# G882X.net
KiCad netlist of a schematic drawn in EAGLE
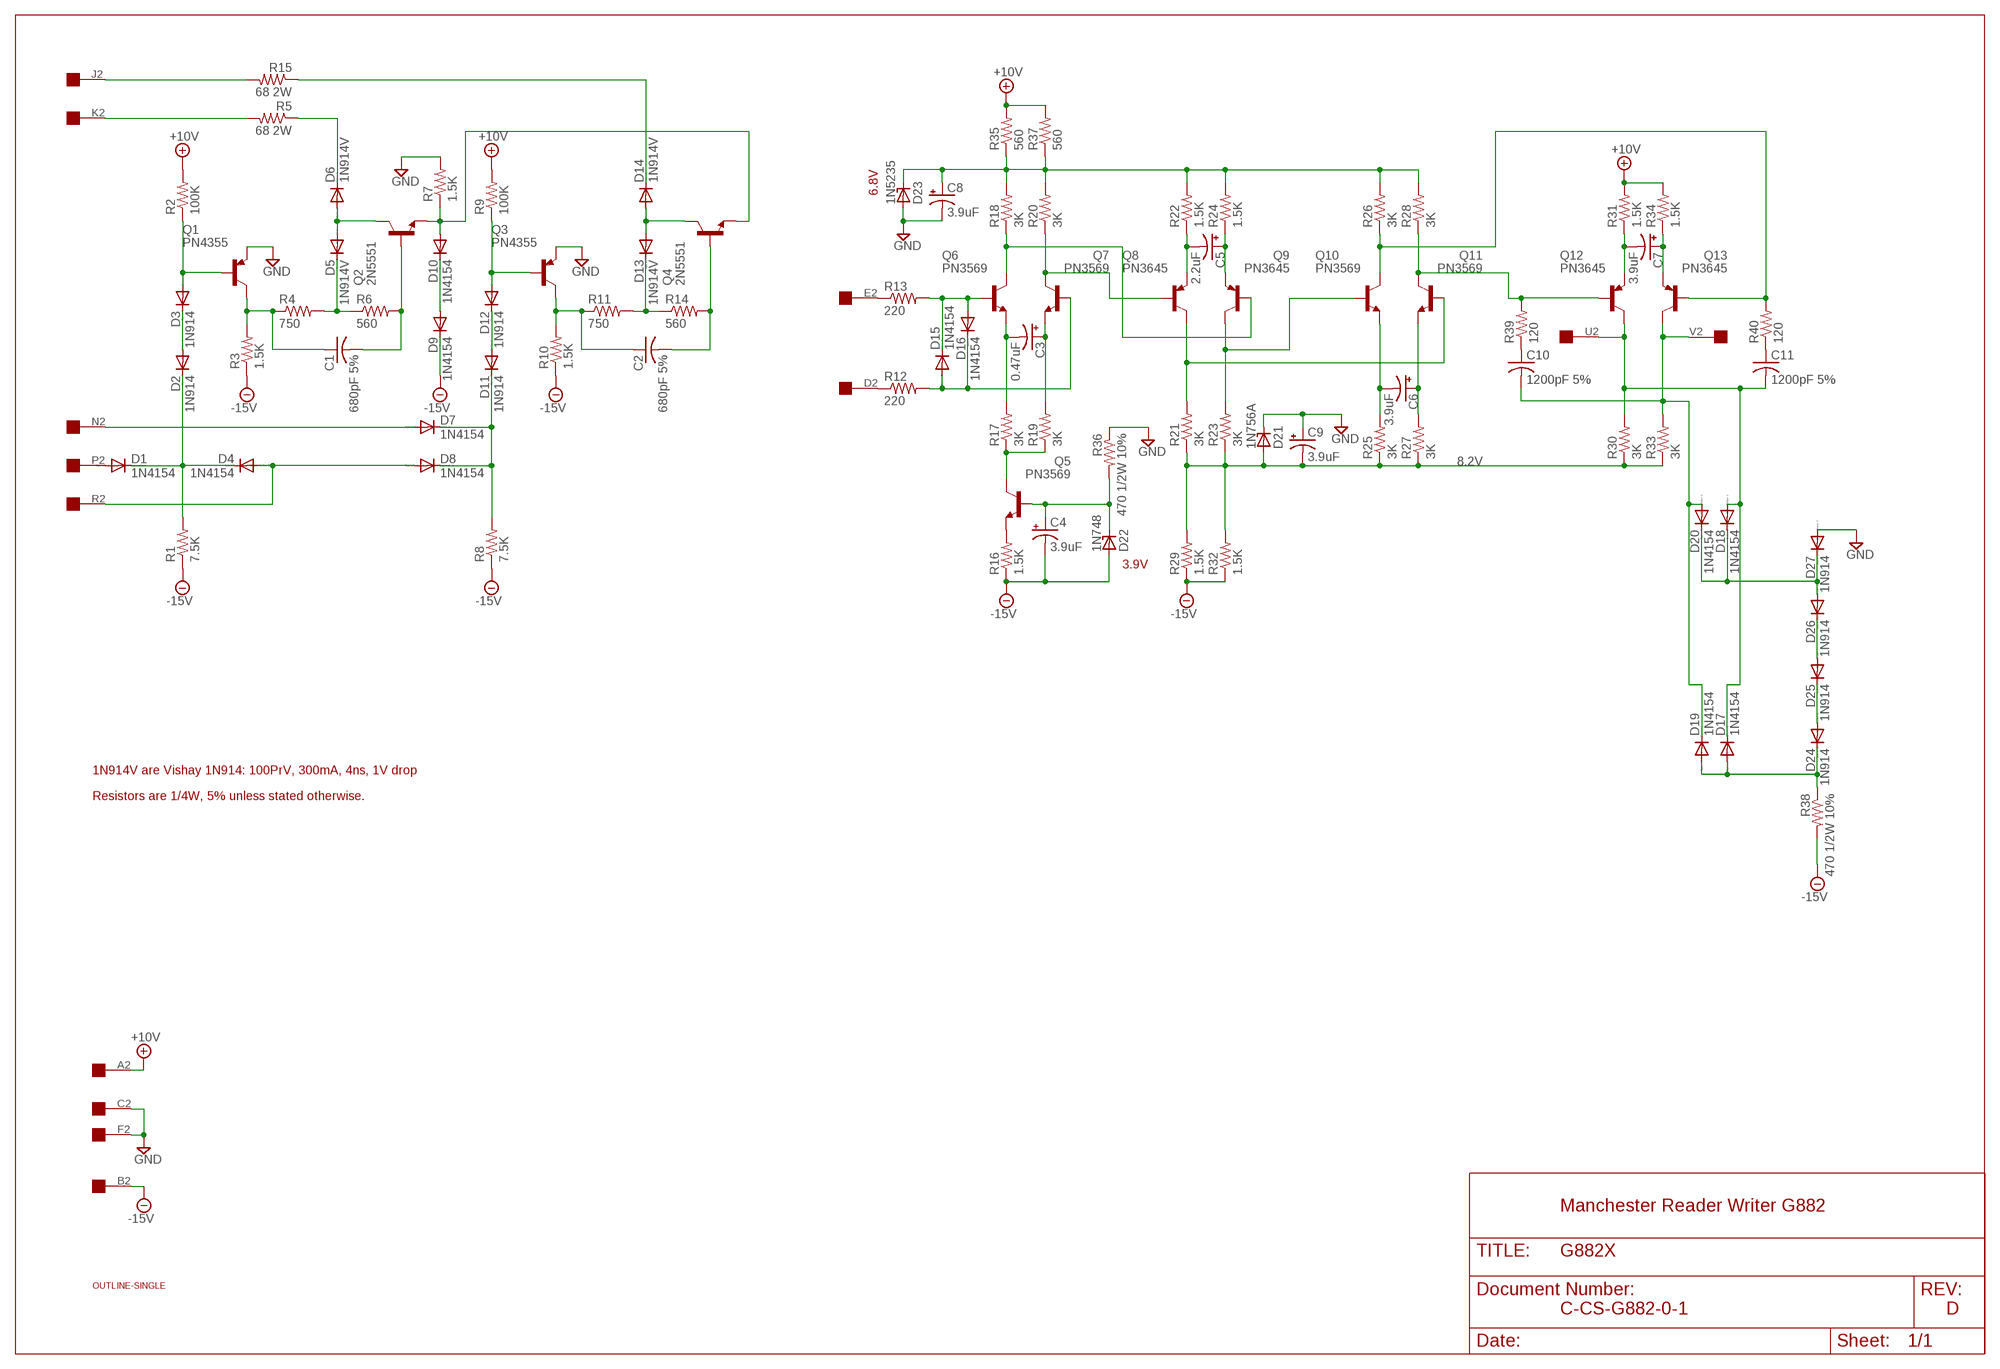
[diagram p0: schematic, sheet 1]

(export (version "E")
  (design (tool "Eeschema 10.0.6"))
  (components
    (comp (ref "C1")
      (value "680pF 5%")
      (footprint "eagle-import:C050-025X075")
      (libsource (lib "eagle-import") (part "C-US050-025X075"))
    )
    (comp (ref "C2")
      (value "680pF 5%")
      (footprint "eagle-import:C050-025X075")
      (libsource (lib "eagle-import") (part "C-US050-025X075"))
    )
    (comp (ref "C3")
      (value "0.47uF")
      (footprint "eagle-import:E12-4")
      (libsource (lib "eagle-import") (part "CPOL-USE12-4AXIAL"))
    )
    (comp (ref "C4")
      (value "3.9uF")
      (footprint "eagle-import:E12-4")
      (libsource (lib "eagle-import") (part "CPOL-USE12-4AXIAL"))
    )
    (comp (ref "C5")
      (value "2.2uF")
      (footprint "eagle-import:E12-4")
      (libsource (lib "eagle-import") (part "CPOL-USE12-4AXIAL"))
    )
    (comp (ref "C6")
      (value "3.9uF")
      (footprint "eagle-import:E12-4")
      (libsource (lib "eagle-import") (part "CPOL-USE12-4AXIAL"))
    )
    (comp (ref "C7")
      (value "3.9uF")
      (footprint "eagle-import:E12-4")
      (libsource (lib "eagle-import") (part "CPOL-USE12-4AXIAL"))
    )
    (comp (ref "C8")
      (value "3.9uF")
      (footprint "eagle-import:E12-4")
      (libsource (lib "eagle-import") (part "CPOL-USE12-4AXIAL"))
    )
    (comp (ref "C9")
      (value "3.9uF")
      (footprint "eagle-import:E12-4")
      (libsource (lib "eagle-import") (part "CPOL-USE12-4AXIAL"))
    )
    (comp (ref "C10")
      (value "1200pF 5%")
      (footprint "eagle-import:C050-025X075")
      (libsource (lib "eagle-import") (part "C-US050-025X075"))
    )
    (comp (ref "C11")
      (value "1200pF 5%")
      (footprint "eagle-import:C050-025X075")
      (libsource (lib "eagle-import") (part "C-US050-025X075"))
    )
    (comp (ref "D1")
      (value "1N4154")
      (footprint "eagle-import:DO35-10")
      (libsource (lib "eagle-import") (part "1N4148DO35-10"))
    )
    (comp (ref "D2")
      (value "1N914")
      (footprint "eagle-import:DO35-10")
      (libsource (lib "eagle-import") (part "1N4148DO35-10"))
    )
    (comp (ref "D3")
      (value "1N914")
      (footprint "eagle-import:DO35-10")
      (libsource (lib "eagle-import") (part "1N4148DO35-10"))
    )
    (comp (ref "D4")
      (value "1N4154")
      (footprint "eagle-import:DO35-10")
      (libsource (lib "eagle-import") (part "1N4148DO35-10"))
    )
    (comp (ref "D5")
      (value "1N914V")
      (footprint "eagle-import:DO35-10")
      (libsource (lib "eagle-import") (part "1N4148DO35-10"))
    )
    (comp (ref "D6")
      (value "1N914V")
      (footprint "eagle-import:DO35-10")
      (libsource (lib "eagle-import") (part "1N4148DO35-10"))
    )
    (comp (ref "D7")
      (value "1N4154")
      (footprint "eagle-import:DO35-10")
      (libsource (lib "eagle-import") (part "1N4148DO35-10"))
    )
    (comp (ref "D8")
      (value "1N4154")
      (footprint "eagle-import:DO35-10")
      (libsource (lib "eagle-import") (part "1N4148DO35-10"))
    )
    (comp (ref "D9")
      (value "1N4154")
      (footprint "eagle-import:DO35-10")
      (libsource (lib "eagle-import") (part "1N4148DO35-10"))
    )
    (comp (ref "D10")
      (value "1N4154")
      (footprint "eagle-import:DO35-10")
      (libsource (lib "eagle-import") (part "1N4148DO35-10"))
    )
    (comp (ref "D11")
      (value "1N914")
      (footprint "eagle-import:DO35-10")
      (libsource (lib "eagle-import") (part "1N4148DO35-10"))
    )
    (comp (ref "D12")
      (value "1N914")
      (footprint "eagle-import:DO35-10")
      (libsource (lib "eagle-import") (part "1N4148DO35-10"))
    )
    (comp (ref "D13")
      (value "1N914V")
      (footprint "eagle-import:DO35-10")
      (libsource (lib "eagle-import") (part "1N4148DO35-10"))
    )
    (comp (ref "D14")
      (value "1N914V")
      (footprint "eagle-import:DO35-10")
      (libsource (lib "eagle-import") (part "1N4148DO35-10"))
    )
    (comp (ref "D15")
      (value "1N4154")
      (footprint "eagle-import:DO35-10")
      (libsource (lib "eagle-import") (part "1N4148DO35-10"))
    )
    (comp (ref "D16")
      (value "1N4154")
      (footprint "eagle-import:DO35-10")
      (libsource (lib "eagle-import") (part "1N4148DO35-10"))
    )
    (comp (ref "D17")
      (value "1N4154")
      (footprint "eagle-import:DO35-10")
      (libsource (lib "eagle-import") (part "1N4148DO35-10"))
    )
    (comp (ref "D18")
      (value "1N4154")
      (footprint "eagle-import:DO35-10")
      (libsource (lib "eagle-import") (part "1N4148DO35-10"))
    )
    (comp (ref "D19")
      (value "1N4154")
      (footprint "eagle-import:DO35-10")
      (libsource (lib "eagle-import") (part "1N4148DO35-10"))
    )
    (comp (ref "D20")
      (value "1N4154")
      (footprint "eagle-import:DO35-10")
      (libsource (lib "eagle-import") (part "1N4148DO35-10"))
    )
    (comp (ref "D21")
      (value "1N756A")
      (footprint "eagle-import:DO35Z10")
      (libsource (lib "eagle-import") (part "ZENER-DIODEDO35Z10"))
    )
    (comp (ref "D22")
      (value "1N748")
      (footprint "eagle-import:DO35Z10")
      (libsource (lib "eagle-import") (part "ZENER-DIODEDO35Z10"))
    )
    (comp (ref "D23")
      (value "1N5235")
      (footprint "eagle-import:DO35Z10")
      (libsource (lib "eagle-import") (part "ZENER-DIODEDO35Z10"))
    )
    (comp (ref "D24")
      (value "1N914")
      (footprint "eagle-import:DO35-10")
      (libsource (lib "eagle-import") (part "1N4148DO35-10"))
    )
    (comp (ref "D25")
      (value "1N914")
      (footprint "eagle-import:DO35-10")
      (libsource (lib "eagle-import") (part "1N4148DO35-10"))
    )
    (comp (ref "D26")
      (value "1N914")
      (footprint "eagle-import:DO35-10")
      (libsource (lib "eagle-import") (part "1N4148DO35-10"))
    )
    (comp (ref "D27")
      (value "1N914")
      (footprint "eagle-import:DO35-10")
      (libsource (lib "eagle-import") (part "1N4148DO35-10"))
    )
    (comp (ref "Q1")
      (value "PN4355")
      (footprint "eagle-import:TO39")
      (libsource (lib "eagle-import") (part "2N3635"))
    )
    (comp (ref "Q2")
      (value "2N5551")
      (footprint "eagle-import:TO5")
      (libsource (lib "eagle-import") (part "2N2102"))
    )
    (comp (ref "Q3")
      (value "PN4355")
      (footprint "eagle-import:TO39")
      (libsource (lib "eagle-import") (part "2N3635"))
    )
    (comp (ref "Q4")
      (value "2N5551")
      (footprint "eagle-import:TO5")
      (libsource (lib "eagle-import") (part "2N2102"))
    )
    (comp (ref "Q5")
      (value "PN3569")
      (footprint "eagle-import:TO5")
      (libsource (lib "eagle-import") (part "2N2102"))
    )
    (comp (ref "Q6")
      (value "PN3569")
      (footprint "eagle-import:TO5")
      (libsource (lib "eagle-import") (part "2N2102"))
    )
    (comp (ref "Q7")
      (value "PN3569")
      (footprint "eagle-import:TO5")
      (libsource (lib "eagle-import") (part "2N2102"))
    )
    (comp (ref "Q8")
      (value "PN3645")
      (footprint "eagle-import:TO39")
      (libsource (lib "eagle-import") (part "2N3635"))
    )
    (comp (ref "Q9")
      (value "PN3645")
      (footprint "eagle-import:TO39")
      (libsource (lib "eagle-import") (part "2N3635"))
    )
    (comp (ref "Q10")
      (value "PN3569")
      (footprint "eagle-import:TO5")
      (libsource (lib "eagle-import") (part "2N2102"))
    )
    (comp (ref "Q11")
      (value "PN3569")
      (footprint "eagle-import:TO5")
      (libsource (lib "eagle-import") (part "2N2102"))
    )
    (comp (ref "Q12")
      (value "PN3645")
      (footprint "eagle-import:TO39")
      (libsource (lib "eagle-import") (part "2N3635"))
    )
    (comp (ref "Q13")
      (value "PN3645")
      (footprint "eagle-import:TO39")
      (libsource (lib "eagle-import") (part "2N3635"))
    )
    (comp (ref "R1")
      (value "7.5K")
      (footprint "eagle-import:0207_10")
      (libsource (lib "eagle-import") (part "R-US_0207/10"))
    )
    (comp (ref "R2")
      (value "100K")
      (footprint "eagle-import:0207_10")
      (libsource (lib "eagle-import") (part "R-US_0207/10"))
    )
    (comp (ref "R3")
      (value "1.5K")
      (footprint "eagle-import:0207_10")
      (libsource (lib "eagle-import") (part "R-US_0207/10"))
    )
    (comp (ref "R4")
      (value "750")
      (footprint "eagle-import:0207_10")
      (libsource (lib "eagle-import") (part "R-US_0207/10"))
    )
    (comp (ref "R5")
      (value "68 2W")
      (footprint "eagle-import:P0817_22")
      (libsource (lib "eagle-import") (part "R-US_0817/22"))
    )
    (comp (ref "R6")
      (value "560")
      (footprint "eagle-import:0207_10")
      (libsource (lib "eagle-import") (part "R-US_0207/10"))
    )
    (comp (ref "R7")
      (value "1.5K")
      (footprint "eagle-import:0207_10")
      (libsource (lib "eagle-import") (part "R-US_0207/10"))
    )
    (comp (ref "R8")
      (value "7.5K")
      (footprint "eagle-import:0207_10")
      (libsource (lib "eagle-import") (part "R-US_0207/10"))
    )
    (comp (ref "R9")
      (value "100K")
      (footprint "eagle-import:0207_10")
      (libsource (lib "eagle-import") (part "R-US_0207/10"))
    )
    (comp (ref "R10")
      (value "1.5K")
      (footprint "eagle-import:0207_10")
      (libsource (lib "eagle-import") (part "R-US_0207/10"))
    )
    (comp (ref "R11")
      (value "750")
      (footprint "eagle-import:0207_10")
      (libsource (lib "eagle-import") (part "R-US_0207/10"))
    )
    (comp (ref "R12")
      (value "220")
      (footprint "eagle-import:0207_10")
      (libsource (lib "eagle-import") (part "R-US_0207/10"))
    )
    (comp (ref "R13")
      (value "220")
      (footprint "eagle-import:0207_10")
      (libsource (lib "eagle-import") (part "R-US_0207/10"))
    )
    (comp (ref "R14")
      (value "560")
      (footprint "eagle-import:0207_10")
      (libsource (lib "eagle-import") (part "R-US_0207/10"))
    )
    (comp (ref "R15")
      (value "68 2W")
      (footprint "eagle-import:P0817_22")
      (libsource (lib "eagle-import") (part "R-US_0817/22"))
    )
    (comp (ref "R16")
      (value "1.5K")
      (footprint "eagle-import:0207_10")
      (libsource (lib "eagle-import") (part "R-US_0207/10"))
    )
    (comp (ref "R17")
      (value "3K")
      (footprint "eagle-import:0207_10")
      (libsource (lib "eagle-import") (part "R-US_0207/10"))
    )
    (comp (ref "R18")
      (value "3K")
      (footprint "eagle-import:0207_10")
      (libsource (lib "eagle-import") (part "R-US_0207/10"))
    )
    (comp (ref "R19")
      (value "3K")
      (footprint "eagle-import:0207_10")
      (libsource (lib "eagle-import") (part "R-US_0207/10"))
    )
    (comp (ref "R20")
      (value "3K")
      (footprint "eagle-import:0207_10")
      (libsource (lib "eagle-import") (part "R-US_0207/10"))
    )
    (comp (ref "R21")
      (value "3K")
      (footprint "eagle-import:0207_10")
      (libsource (lib "eagle-import") (part "R-US_0207/10"))
    )
    (comp (ref "R22")
      (value "1.5K")
      (footprint "eagle-import:0207_10")
      (libsource (lib "eagle-import") (part "R-US_0207/10"))
    )
    (comp (ref "R23")
      (value "3K")
      (footprint "eagle-import:0207_10")
      (libsource (lib "eagle-import") (part "R-US_0207/10"))
    )
    (comp (ref "R24")
      (value "1.5K")
      (footprint "eagle-import:0207_10")
      (libsource (lib "eagle-import") (part "R-US_0207/10"))
    )
    (comp (ref "R25")
      (value "3K")
      (footprint "eagle-import:0207_10")
      (libsource (lib "eagle-import") (part "R-US_0207/10"))
    )
    (comp (ref "R26")
      (value "3K")
      (footprint "eagle-import:0207_10")
      (libsource (lib "eagle-import") (part "R-US_0207/10"))
    )
    (comp (ref "R27")
      (value "3K")
      (footprint "eagle-import:0207_10")
      (libsource (lib "eagle-import") (part "R-US_0207/10"))
    )
    (comp (ref "R28")
      (value "3K")
      (footprint "eagle-import:0207_10")
      (libsource (lib "eagle-import") (part "R-US_0207/10"))
    )
    (comp (ref "R29")
      (value "1.5K")
      (footprint "eagle-import:0207_10")
      (libsource (lib "eagle-import") (part "R-US_0207/10"))
    )
    (comp (ref "R30")
      (value "3K")
      (footprint "eagle-import:0207_10")
      (libsource (lib "eagle-import") (part "R-US_0207/10"))
    )
    (comp (ref "R31")
      (value "1.5K")
      (footprint "eagle-import:0207_10")
      (libsource (lib "eagle-import") (part "R-US_0207/10"))
    )
    (comp (ref "R32")
      (value "1.5K")
      (footprint "eagle-import:0207_10")
      (libsource (lib "eagle-import") (part "R-US_0207/10"))
    )
    (comp (ref "R33")
      (value "3K")
      (footprint "eagle-import:0207_10")
      (libsource (lib "eagle-import") (part "R-US_0207/10"))
    )
    (comp (ref "R34")
      (value "1.5K")
      (footprint "eagle-import:0207_10")
      (libsource (lib "eagle-import") (part "R-US_0207/10"))
    )
    (comp (ref "R35")
      (value "560")
      (footprint "eagle-import:0207_10")
      (libsource (lib "eagle-import") (part "R-US_0207/10"))
    )
    (comp (ref "R36")
      (value "470 1/2W 10%")
      (footprint "eagle-import:0309_12")
      (libsource (lib "eagle-import") (part "R-US_0309/12"))
    )
    (comp (ref "R37")
      (value "560")
      (footprint "eagle-import:0207_10")
      (libsource (lib "eagle-import") (part "R-US_0207/10"))
    )
    (comp (ref "R38")
      (value "470 1/2W 10%")
      (footprint "eagle-import:0309_12")
      (libsource (lib "eagle-import") (part "R-US_0309/12"))
    )
    (comp (ref "R39")
      (value "120")
      (footprint "eagle-import:0207_10")
      (libsource (lib "eagle-import") (part "R-US_0207/10"))
    )
    (comp (ref "R40")
      (value "120")
      (footprint "eagle-import:0207_10")
      (libsource (lib "eagle-import") (part "R-US_0207/10"))
    )
    (comp (ref "U$1")
      (value "OUTLINE-SINGLE")
      (footprint "eagle-import:SINGLE")
      (libsource (lib "eagle-import") (part "OUTLINE-SINGLE"))
    )
    (comp (ref "U$2")
      (value "EDGE-1")
      (footprint "eagle-import:EDGE-CON1")
      (libsource (lib "eagle-import") (part "EDGE-1"))
    )
  )
  (nets
    (net (code "1") (name "+10V") (class "Default")
      (node (ref "R2") (pin "2") (pinfunction "2_2") (pintype "passive"))
      (node (ref "R31") (pin "2") (pinfunction "2_2") (pintype "passive"))
      (node (ref "R34") (pin "2") (pinfunction "2_2") (pintype "passive"))
      (node (ref "R35") (pin "2") (pinfunction "2_2") (pintype "passive"))
      (node (ref "R37") (pin "2") (pinfunction "2_2") (pintype "passive"))
      (node (ref "R9") (pin "2") (pinfunction "2_2") (pintype "passive"))
      (node (ref "U$2") (pin "A2") (pinfunction "1_A2") (pintype "bidirectional"))
    )
    (net (code "2") (name "-15V") (class "Default")
      (node (ref "C4") (pin "-") (pinfunction "-_-") (pintype "passive"))
      (node (ref "D22") (pin "A") (pinfunction "A_A") (pintype "passive"))
      (node (ref "D9") (pin "C") (pinfunction "C_C") (pintype "passive"))
      (node (ref "R1") (pin "1") (pinfunction "1_1") (pintype "passive"))
      (node (ref "R10") (pin "1") (pinfunction "1_1") (pintype "passive"))
      (node (ref "R16") (pin "1") (pinfunction "1_1") (pintype "passive"))
      (node (ref "R29") (pin "1") (pinfunction "1_1") (pintype "passive"))
      (node (ref "R3") (pin "1") (pinfunction "1_1") (pintype "passive"))
      (node (ref "R32") (pin "1") (pinfunction "1_1") (pintype "passive"))
      (node (ref "R38") (pin "2") (pinfunction "2_2") (pintype "passive"))
      (node (ref "R8") (pin "1") (pinfunction "1_1") (pintype "passive"))
      (node (ref "U$2") (pin "B2") (pinfunction "1_B2") (pintype "bidirectional"))
    )
    (net (code "3") (name "/8.2V") (class "Default")
      (node (ref "C9") (pin "-") (pinfunction "-_-") (pintype "passive"))
      (node (ref "D21") (pin "A") (pinfunction "A_A") (pintype "passive"))
      (node (ref "R21") (pin "1") (pinfunction "1_1") (pintype "passive"))
      (node (ref "R23") (pin "1") (pinfunction "1_1") (pintype "passive"))
      (node (ref "R25") (pin "1") (pinfunction "1_1") (pintype "passive"))
      (node (ref "R27") (pin "1") (pinfunction "1_1") (pintype "passive"))
      (node (ref "R29") (pin "2") (pinfunction "2_2") (pintype "passive"))
      (node (ref "R30") (pin "1") (pinfunction "1_1") (pintype "passive"))
      (node (ref "R32") (pin "2") (pinfunction "2_2") (pintype "passive"))
      (node (ref "R33") (pin "1") (pinfunction "1_1") (pintype "passive"))
    )
    (net (code "4") (name "GND") (class "Default")
      (node (ref "C8") (pin "-") (pinfunction "-_-") (pintype "passive"))
      (node (ref "C9") (pin "+") (pinfunction "+_+") (pintype "passive"))
      (node (ref "D21") (pin "C") (pinfunction "C_C") (pintype "passive"))
      (node (ref "D23") (pin "A") (pinfunction "A_A") (pintype "passive"))
      (node (ref "D27") (pin "A") (pinfunction "A_A") (pintype "passive"))
      (node (ref "Q1") (pin "1") (pinfunction "E_1") (pintype "passive"))
      (node (ref "Q3") (pin "1") (pinfunction "E_1") (pintype "passive"))
      (node (ref "R36") (pin "1") (pinfunction "1_1") (pintype "passive"))
      (node (ref "R7") (pin "2") (pinfunction "2_2") (pintype "passive"))
      (node (ref "U$2") (pin "C2") (pinfunction "1_C2") (pintype "bidirectional"))
      (node (ref "U$2") (pin "F2") (pinfunction "1_F2") (pintype "bidirectional"))
    )
    (net (code "5") (name "Net-(C8-Pad+)") (class "Default")
      (node (ref "C8") (pin "+") (pinfunction "+_+") (pintype "passive"))
      (node (ref "D23") (pin "C") (pinfunction "C_C") (pintype "passive"))
      (node (ref "R18") (pin "2") (pinfunction "2_2") (pintype "passive"))
      (node (ref "R20") (pin "2") (pinfunction "2_2") (pintype "passive"))
      (node (ref "R22") (pin "2") (pinfunction "2_2") (pintype "passive"))
      (node (ref "R24") (pin "2") (pinfunction "2_2") (pintype "passive"))
      (node (ref "R26") (pin "2") (pinfunction "2_2") (pintype "passive"))
      (node (ref "R28") (pin "2") (pinfunction "2_2") (pintype "passive"))
      (node (ref "R35") (pin "1") (pinfunction "1_1") (pintype "passive"))
      (node (ref "R37") (pin "1") (pinfunction "1_1") (pintype "passive"))
    )
    (net (code "6") (name "Net-(C10-Pad1)") (class "Default")
      (node (ref "C10") (pin "1") (pinfunction "1_1") (pintype "passive"))
      (node (ref "R39") (pin "1") (pinfunction "1_1") (pintype "passive"))
    )
    (net (code "7") (name "Net-(C11-Pad1)") (class "Default")
      (node (ref "C11") (pin "1") (pinfunction "1_1") (pintype "passive"))
      (node (ref "R40") (pin "1") (pinfunction "1_1") (pintype "passive"))
    )
    (net (code "8") (name "Net-(D1-PadC)") (class "Default")
      (node (ref "D1") (pin "C") (pinfunction "C_C") (pintype "passive"))
      (node (ref "D2") (pin "C") (pinfunction "C_C") (pintype "passive"))
      (node (ref "D4") (pin "C") (pinfunction "C_C") (pintype "passive"))
      (node (ref "R1") (pin "2") (pinfunction "2_2") (pintype "passive"))
    )
    (net (code "9") (name "Net-(D2-PadA)") (class "Default")
      (node (ref "D2") (pin "A") (pinfunction "A_A") (pintype "passive"))
      (node (ref "D3") (pin "C") (pinfunction "C_C") (pintype "passive"))
    )
    (net (code "10") (name "Net-(D5-PadC)") (class "Default")
      (node (ref "D5") (pin "C") (pinfunction "C_C") (pintype "passive"))
      (node (ref "R4") (pin "2") (pinfunction "2_2") (pintype "passive"))
      (node (ref "R6") (pin "1") (pinfunction "1_1") (pintype "passive"))
    )
    (net (code "11") (name "Net-(D6-PadC)") (class "Default")
      (node (ref "D6") (pin "C") (pinfunction "C_C") (pintype "passive"))
      (node (ref "R5") (pin "1") (pinfunction "1_1") (pintype "passive"))
    )
    (net (code "12") (name "Net-(D10-PadC)") (class "Default")
      (node (ref "D10") (pin "C") (pinfunction "C_C") (pintype "passive"))
      (node (ref "D9") (pin "A") (pinfunction "A_A") (pintype "passive"))
    )
    (net (code "13") (name "Net-(D11-PadA)") (class "Default")
      (node (ref "D11") (pin "A") (pinfunction "A_A") (pintype "passive"))
      (node (ref "D12") (pin "C") (pinfunction "C_C") (pintype "passive"))
    )
    (net (code "14") (name "Net-(D11-PadC)") (class "Default")
      (node (ref "D11") (pin "C") (pinfunction "C_C") (pintype "passive"))
      (node (ref "D7") (pin "C") (pinfunction "C_C") (pintype "passive"))
      (node (ref "D8") (pin "C") (pinfunction "C_C") (pintype "passive"))
      (node (ref "R8") (pin "2") (pinfunction "2_2") (pintype "passive"))
    )
    (net (code "15") (name "Net-(D13-PadC)") (class "Default")
      (node (ref "D13") (pin "C") (pinfunction "C_C") (pintype "passive"))
      (node (ref "R11") (pin "2") (pinfunction "2_2") (pintype "passive"))
      (node (ref "R14") (pin "1") (pinfunction "1_1") (pintype "passive"))
    )
    (net (code "16") (name "Net-(D14-PadC)") (class "Default")
      (node (ref "D14") (pin "C") (pinfunction "C_C") (pintype "passive"))
      (node (ref "R15") (pin "1") (pinfunction "1_1") (pintype "passive"))
    )
    (net (code "17") (name "Net-(D17-PadA)") (class "Default")
      (node (ref "D17") (pin "A") (pinfunction "A_A") (pintype "passive"))
      (node (ref "D19") (pin "A") (pinfunction "A_A") (pintype "passive"))
      (node (ref "D24") (pin "C") (pinfunction "C_C") (pintype "passive"))
      (node (ref "R38") (pin "1") (pinfunction "1_1") (pintype "passive"))
    )
    (net (code "18") (name "Net-(D18-PadC)") (class "Default")
      (node (ref "D18") (pin "C") (pinfunction "C_C") (pintype "passive"))
      (node (ref "D20") (pin "C") (pinfunction "C_C") (pintype "passive"))
      (node (ref "D26") (pin "A") (pinfunction "A_A") (pintype "passive"))
      (node (ref "D27") (pin "C") (pinfunction "C_C") (pintype "passive"))
    )
    (net (code "19") (name "Net-(D24-PadA)") (class "Default")
      (node (ref "D24") (pin "A") (pinfunction "A_A") (pintype "passive"))
      (node (ref "D25") (pin "C") (pinfunction "C_C") (pintype "passive"))
    )
    (net (code "20") (name "Net-(D25-PadA)") (class "Default")
      (node (ref "D25") (pin "A") (pinfunction "A_A") (pintype "passive"))
      (node (ref "D26") (pin "C") (pinfunction "C_C") (pintype "passive"))
    )
    (net (code "21") (name "Net-(Q1-B)") (class "Default")
      (node (ref "D3") (pin "A") (pinfunction "A_A") (pintype "passive"))
      (node (ref "Q1") (pin "2") (pinfunction "B_2") (pintype "passive"))
      (node (ref "R2") (pin "1") (pinfunction "1_1") (pintype "passive"))
    )
    (net (code "22") (name "Net-(Q1-C)") (class "Default")
      (node (ref "C1") (pin "1") (pinfunction "1_1") (pintype "passive"))
      (node (ref "Q1") (pin "3") (pinfunction "C_3") (pintype "passive"))
      (node (ref "R3") (pin "2") (pinfunction "2_2") (pintype "passive"))
      (node (ref "R4") (pin "1") (pinfunction "1_1") (pintype "passive"))
    )
    (net (code "23") (name "Net-(Q2-B)") (class "Default")
      (node (ref "C1") (pin "2") (pinfunction "2_2") (pintype "passive"))
      (node (ref "Q2") (pin "2") (pinfunction "B_2") (pintype "passive"))
      (node (ref "R6") (pin "2") (pinfunction "2_2") (pintype "passive"))
    )
    (net (code "24") (name "Net-(Q2-C)") (class "Default")
      (node (ref "D5") (pin "A") (pinfunction "A_A") (pintype "passive"))
      (node (ref "D6") (pin "A") (pinfunction "A_A") (pintype "passive"))
      (node (ref "Q2") (pin "3") (pinfunction "C_3") (pintype "passive"))
    )
    (net (code "25") (name "Net-(Q2-E)") (class "Default")
      (node (ref "D10") (pin "A") (pinfunction "A_A") (pintype "passive"))
      (node (ref "Q2") (pin "1") (pinfunction "E_1") (pintype "passive"))
      (node (ref "Q4") (pin "1") (pinfunction "E_1") (pintype "passive"))
      (node (ref "R7") (pin "1") (pinfunction "1_1") (pintype "passive"))
    )
    (net (code "26") (name "Net-(Q3-B)") (class "Default")
      (node (ref "D12") (pin "A") (pinfunction "A_A") (pintype "passive"))
      (node (ref "Q3") (pin "2") (pinfunction "B_2") (pintype "passive"))
      (node (ref "R9") (pin "1") (pinfunction "1_1") (pintype "passive"))
    )
    (net (code "27") (name "Net-(Q3-C)") (class "Default")
      (node (ref "C2") (pin "1") (pinfunction "1_1") (pintype "passive"))
      (node (ref "Q3") (pin "3") (pinfunction "C_3") (pintype "passive"))
      (node (ref "R10") (pin "2") (pinfunction "2_2") (pintype "passive"))
      (node (ref "R11") (pin "1") (pinfunction "1_1") (pintype "passive"))
    )
    (net (code "28") (name "Net-(Q4-B)") (class "Default")
      (node (ref "C2") (pin "2") (pinfunction "2_2") (pintype "passive"))
      (node (ref "Q4") (pin "2") (pinfunction "B_2") (pintype "passive"))
      (node (ref "R14") (pin "2") (pinfunction "2_2") (pintype "passive"))
    )
    (net (code "29") (name "Net-(Q4-C)") (class "Default")
      (node (ref "D13") (pin "A") (pinfunction "A_A") (pintype "passive"))
      (node (ref "D14") (pin "A") (pinfunction "A_A") (pintype "passive"))
      (node (ref "Q4") (pin "3") (pinfunction "C_3") (pintype "passive"))
    )
    (net (code "30") (name "Net-(Q5-B)") (class "Default")
      (node (ref "C4") (pin "+") (pinfunction "+_+") (pintype "passive"))
      (node (ref "D22") (pin "C") (pinfunction "C_C") (pintype "passive"))
      (node (ref "Q5") (pin "2") (pinfunction "B_2") (pintype "passive"))
      (node (ref "R36") (pin "2") (pinfunction "2_2") (pintype "passive"))
    )
    (net (code "31") (name "Net-(Q5-C)") (class "Default")
      (node (ref "Q5") (pin "3") (pinfunction "C_3") (pintype "passive"))
      (node (ref "R17") (pin "1") (pinfunction "1_1") (pintype "passive"))
      (node (ref "R19") (pin "1") (pinfunction "1_1") (pintype "passive"))
    )
    (net (code "32") (name "Net-(Q5-E)") (class "Default")
      (node (ref "Q5") (pin "1") (pinfunction "E_1") (pintype "passive"))
      (node (ref "R16") (pin "2") (pinfunction "2_2") (pintype "passive"))
    )
    (net (code "33") (name "Net-(Q6-B)") (class "Default")
      (node (ref "D15") (pin "C") (pinfunction "C_C") (pintype "passive"))
      (node (ref "D16") (pin "A") (pinfunction "A_A") (pintype "passive"))
      (node (ref "Q6") (pin "2") (pinfunction "B_2") (pintype "passive"))
      (node (ref "R13") (pin "2") (pinfunction "2_2") (pintype "passive"))
    )
    (net (code "34") (name "Net-(Q6-C)") (class "Default")
      (node (ref "Q6") (pin "3") (pinfunction "C_3") (pintype "passive"))
      (node (ref "Q9") (pin "2") (pinfunction "B_2") (pintype "passive"))
      (node (ref "R18") (pin "1") (pinfunction "1_1") (pintype "passive"))
    )
    (net (code "35") (name "Net-(Q6-E)") (class "Default")
      (node (ref "C3") (pin "-") (pinfunction "-_-") (pintype "passive"))
      (node (ref "Q6") (pin "1") (pinfunction "E_1") (pintype "passive"))
      (node (ref "R17") (pin "2") (pinfunction "2_2") (pintype "passive"))
    )
    (net (code "36") (name "Net-(Q7-B)") (class "Default")
      (node (ref "D15") (pin "A") (pinfunction "A_A") (pintype "passive"))
      (node (ref "D16") (pin "C") (pinfunction "C_C") (pintype "passive"))
      (node (ref "Q7") (pin "2") (pinfunction "B_2") (pintype "passive"))
      (node (ref "R12") (pin "2") (pinfunction "2_2") (pintype "passive"))
    )
    (net (code "37") (name "Net-(Q7-C)") (class "Default")
      (node (ref "Q7") (pin "3") (pinfunction "C_3") (pintype "passive"))
      (node (ref "Q8") (pin "2") (pinfunction "B_2") (pintype "passive"))
      (node (ref "R20") (pin "1") (pinfunction "1_1") (pintype "passive"))
    )
    (net (code "38") (name "Net-(Q7-E)") (class "Default")
      (node (ref "C3") (pin "+") (pinfunction "+_+") (pintype "passive"))
      (node (ref "Q7") (pin "1") (pinfunction "E_1") (pintype "passive"))
      (node (ref "R19") (pin "2") (pinfunction "2_2") (pintype "passive"))
    )
    (net (code "39") (name "Net-(Q8-E)") (class "Default")
      (node (ref "C5") (pin "-") (pinfunction "-_-") (pintype "passive"))
      (node (ref "Q8") (pin "1") (pinfunction "E_1") (pintype "passive"))
      (node (ref "R22") (pin "1") (pinfunction "1_1") (pintype "passive"))
    )
    (net (code "40") (name "Net-(Q9-E)") (class "Default")
      (node (ref "C5") (pin "+") (pinfunction "+_+") (pintype "passive"))
      (node (ref "Q9") (pin "1") (pinfunction "E_1") (pintype "passive"))
      (node (ref "R24") (pin "1") (pinfunction "1_1") (pintype "passive"))
    )
    (net (code "41") (name "Net-(Q10-B)") (class "Default")
      (node (ref "Q10") (pin "2") (pinfunction "B_2") (pintype "passive"))
      (node (ref "Q9") (pin "3") (pinfunction "C_3") (pintype "passive"))
      (node (ref "R23") (pin "2") (pinfunction "2_2") (pintype "passive"))
    )
    (net (code "42") (name "Net-(Q10-C)") (class "Default")
      (node (ref "Q10") (pin "3") (pinfunction "C_3") (pintype "passive"))
      (node (ref "Q13") (pin "2") (pinfunction "B_2") (pintype "passive"))
      (node (ref "R26") (pin "1") (pinfunction "1_1") (pintype "passive"))
      (node (ref "R40") (pin "2") (pinfunction "2_2") (pintype "passive"))
    )
    (net (code "43") (name "Net-(Q10-E)") (class "Default")
      (node (ref "C6") (pin "-") (pinfunction "-_-") (pintype "passive"))
      (node (ref "Q10") (pin "1") (pinfunction "E_1") (pintype "passive"))
      (node (ref "R25") (pin "2") (pinfunction "2_2") (pintype "passive"))
    )
    (net (code "44") (name "Net-(Q11-B)") (class "Default")
      (node (ref "Q11") (pin "2") (pinfunction "B_2") (pintype "passive"))
      (node (ref "Q8") (pin "3") (pinfunction "C_3") (pintype "passive"))
      (node (ref "R21") (pin "2") (pinfunction "2_2") (pintype "passive"))
    )
    (net (code "45") (name "Net-(Q11-C)") (class "Default")
      (node (ref "Q11") (pin "3") (pinfunction "C_3") (pintype "passive"))
      (node (ref "Q12") (pin "2") (pinfunction "B_2") (pintype "passive"))
      (node (ref "R28") (pin "1") (pinfunction "1_1") (pintype "passive"))
      (node (ref "R39") (pin "2") (pinfunction "2_2") (pintype "passive"))
    )
    (net (code "46") (name "Net-(Q11-E)") (class "Default")
      (node (ref "C6") (pin "+") (pinfunction "+_+") (pintype "passive"))
      (node (ref "Q11") (pin "1") (pinfunction "E_1") (pintype "passive"))
      (node (ref "R27") (pin "2") (pinfunction "2_2") (pintype "passive"))
    )
    (net (code "47") (name "Net-(Q12-C)") (class "Default")
      (node (ref "C11") (pin "2") (pinfunction "2_2") (pintype "passive"))
      (node (ref "D17") (pin "C") (pinfunction "C_C") (pintype "passive"))
      (node (ref "D18") (pin "A") (pinfunction "A_A") (pintype "passive"))
      (node (ref "Q12") (pin "3") (pinfunction "C_3") (pintype "passive"))
      (node (ref "R30") (pin "2") (pinfunction "2_2") (pintype "passive"))
      (node (ref "U$2") (pin "U2") (pinfunction "1_U2") (pintype "bidirectional"))
    )
    (net (code "48") (name "Net-(Q12-E)") (class "Default")
      (node (ref "C7") (pin "-") (pinfunction "-_-") (pintype "passive"))
      (node (ref "Q12") (pin "1") (pinfunction "E_1") (pintype "passive"))
      (node (ref "R31") (pin "1") (pinfunction "1_1") (pintype "passive"))
    )
    (net (code "49") (name "Net-(Q13-C)") (class "Default")
      (node (ref "C10") (pin "2") (pinfunction "2_2") (pintype "passive"))
      (node (ref "D19") (pin "C") (pinfunction "C_C") (pintype "passive"))
      (node (ref "D20") (pin "A") (pinfunction "A_A") (pintype "passive"))
      (node (ref "Q13") (pin "3") (pinfunction "C_3") (pintype "passive"))
      (node (ref "R33") (pin "2") (pinfunction "2_2") (pintype "passive"))
      (node (ref "U$2") (pin "V2") (pinfunction "1_V2") (pintype "bidirectional"))
    )
    (net (code "50") (name "Net-(Q13-E)") (class "Default")
      (node (ref "C7") (pin "+") (pinfunction "+_+") (pintype "passive"))
      (node (ref "Q13") (pin "1") (pinfunction "E_1") (pintype "passive"))
      (node (ref "R34") (pin "1") (pinfunction "1_1") (pintype "passive"))
    )
    (net (code "51") (name "Net-(U$2D-1)") (class "Default")
      (node (ref "R12") (pin "1") (pinfunction "1_1") (pintype "passive"))
      (node (ref "U$2") (pin "D2") (pinfunction "1_D2") (pintype "bidirectional"))
    )
    (net (code "52") (name "Net-(U$2E-1)") (class "Default")
      (node (ref "R13") (pin "1") (pinfunction "1_1") (pintype "passive"))
      (node (ref "U$2") (pin "E2") (pinfunction "1_E2") (pintype "bidirectional"))
    )
    (net (code "53") (name "Net-(U$2H-1)") (class "Default")
      (node (ref "R15") (pin "2") (pinfunction "2_2") (pintype "passive"))
      (node (ref "U$2") (pin "J2") (pinfunction "1_J2") (pintype "bidirectional"))
    )
    (net (code "54") (name "Net-(U$2I-1)") (class "Default")
      (node (ref "R5") (pin "2") (pinfunction "2_2") (pintype "passive"))
      (node (ref "U$2") (pin "K2") (pinfunction "1_K2") (pintype "bidirectional"))
    )
    (net (code "55") (name "Net-(U$2L-1)") (class "Default")
      (node (ref "D7") (pin "A") (pinfunction "A_A") (pintype "passive"))
      (node (ref "U$2") (pin "N2") (pinfunction "1_N2") (pintype "bidirectional"))
    )
    (net (code "56") (name "Net-(U$2M-1)") (class "Default")
      (node (ref "D1") (pin "A") (pinfunction "A_A") (pintype "passive"))
      (node (ref "U$2") (pin "P2") (pinfunction "1_P2") (pintype "bidirectional"))
    )
    (net (code "57") (name "Net-(U$2N-1)") (class "Default")
      (node (ref "D4") (pin "A") (pinfunction "A_A") (pintype "passive"))
      (node (ref "D8") (pin "A") (pinfunction "A_A") (pintype "passive"))
      (node (ref "U$2") (pin "R2") (pinfunction "1_R2") (pintype "bidirectional"))
    )
  )
)
